# tx_board.net
KiCad netlist of a schematic drawn in Altium Designer
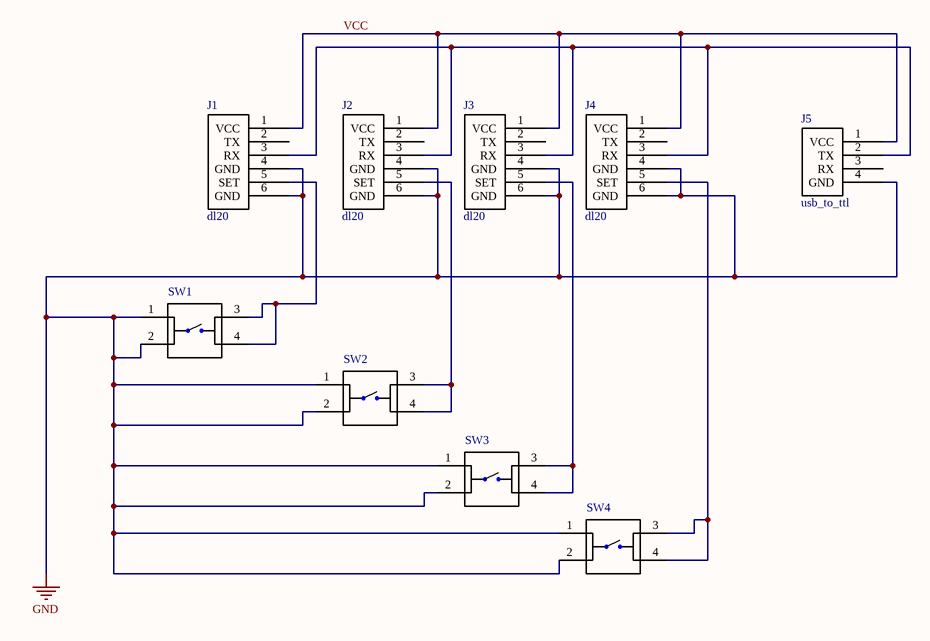
[diagram p0: tx_board.SchDoc]

(export (version "E")
  (design (tool "Eeschema 10.0.6"))
  (components
    (comp (ref "J1") (value "dl20") (footprint "DL20") (libsource (lib "Schlib2") (part "dl20")))
    (comp (ref "J2") (value "dl20") (footprint "DL20") (libsource (lib "Schlib2") (part "dl20")))
    (comp (ref "J3") (value "dl20") (footprint "DL20") (libsource (lib "Schlib2") (part "dl20")))
    (comp (ref "J4") (value "dl20") (footprint "DL20") (libsource (lib "Schlib2") (part "dl20")))
    (comp (ref "J5")
      (value "usb_to_ttl")
      (footprint "USB_TO_TTL")
      (libsource (lib "Schlib2") (part "usb_to_ttl"))
    )
    (comp (ref "SW1")
      (value "1825910-6")
      (footprint "*SW_1825910-6-4")
      (description "FSM4JH=6MM TACT SWITCH, HIGH TEMP")
      (fields (field (name "DIGI-KEY_PART_NUMBER") "450-1650-ND") (field (name "MF") "TE Connectivity"))
      (libsource (lib "1825910-6") (part "1825910-6"))
    )
    (comp (ref "SW2")
      (value "1825910-6")
      (footprint "*SW_1825910-6-4")
      (description "FSM4JH=6MM TACT SWITCH, HIGH TEMP")
      (fields (field (name "DIGI-KEY_PART_NUMBER") "450-1650-ND") (field (name "MF") "TE Connectivity"))
      (libsource (lib "1825910-6") (part "1825910-6"))
    )
    (comp (ref "SW3")
      (value "1825910-6")
      (footprint "*SW_1825910-6-4")
      (description "FSM4JH=6MM TACT SWITCH, HIGH TEMP")
      (fields (field (name "DIGI-KEY_PART_NUMBER") "450-1650-ND") (field (name "MF") "TE Connectivity"))
      (libsource (lib "1825910-6") (part "1825910-6"))
    )
    (comp (ref "SW4")
      (value "1825910-6")
      (footprint "*SW_1825910-6-4")
      (description "FSM4JH=6MM TACT SWITCH, HIGH TEMP")
      (fields (field (name "DIGI-KEY_PART_NUMBER") "450-1650-ND") (field (name "MF") "TE Connectivity"))
      (libsource (lib "1825910-6") (part "1825910-6"))
    )
  )
  (nets
    (net (code "1") (name "/VCC") (class "Default")
      (node (ref "J1") (pin "1") (pinfunction "VCC_1") (pintype "power_in"))
      (node (ref "J2") (pin "1") (pinfunction "VCC_1") (pintype "power_in"))
      (node (ref "J3") (pin "1") (pinfunction "VCC_1") (pintype "power_in"))
      (node (ref "J4") (pin "1") (pinfunction "VCC_1") (pintype "power_in"))
      (node (ref "J5") (pin "1") (pinfunction "VCC_1") (pintype "passive"))
    )
    (net (code "2") (name "GND") (class "Default")
      (node (ref "J1") (pin "4") (pinfunction "GND_4") (pintype "power_in"))
      (node (ref "J1") (pin "6") (pinfunction "GND_6") (pintype "power_in"))
      (node (ref "J2") (pin "4") (pinfunction "GND_4") (pintype "power_in"))
      (node (ref "J2") (pin "6") (pinfunction "GND_6") (pintype "power_in"))
      (node (ref "J3") (pin "4") (pinfunction "GND_4") (pintype "power_in"))
      (node (ref "J3") (pin "6") (pinfunction "GND_6") (pintype "power_in"))
      (node (ref "J4") (pin "4") (pinfunction "GND_4") (pintype "power_in"))
      (node (ref "J4") (pin "6") (pinfunction "GND_6") (pintype "power_in"))
      (node (ref "J5") (pin "4") (pinfunction "GND_4") (pintype "passive"))
      (node (ref "SW1") (pin "1") (pinfunction "1_1") (pintype "passive"))
      (node (ref "SW1") (pin "2") (pinfunction "2_2") (pintype "passive"))
      (node (ref "SW2") (pin "1") (pinfunction "1_1") (pintype "passive"))
      (node (ref "SW2") (pin "2") (pinfunction "2_2") (pintype "passive"))
      (node (ref "SW3") (pin "1") (pinfunction "1_1") (pintype "passive"))
      (node (ref "SW3") (pin "2") (pinfunction "2_2") (pintype "passive"))
      (node (ref "SW4") (pin "1") (pinfunction "1_1") (pintype "passive"))
      (node (ref "SW4") (pin "2") (pinfunction "2_2") (pintype "passive"))
    )
    (net (code "3") (name "Net-(J1-RX)") (class "Default")
      (node (ref "J1") (pin "3") (pinfunction "RX_3") (pintype "passive"))
      (node (ref "J2") (pin "3") (pinfunction "RX_3") (pintype "passive"))
      (node (ref "J3") (pin "3") (pinfunction "RX_3") (pintype "passive"))
      (node (ref "J4") (pin "3") (pinfunction "RX_3") (pintype "passive"))
      (node (ref "J5") (pin "2") (pinfunction "TX_2") (pintype "passive"))
    )
    (net (code "4") (name "Net-(J1-SET)") (class "Default")
      (node (ref "J1") (pin "5") (pinfunction "SET_5") (pintype "passive"))
      (node (ref "SW1") (pin "3") (pinfunction "3_3") (pintype "passive"))
      (node (ref "SW1") (pin "4") (pinfunction "4_4") (pintype "passive"))
    )
    (net (code "5") (name "Net-(J2-SET)") (class "Default")
      (node (ref "J2") (pin "5") (pinfunction "SET_5") (pintype "passive"))
      (node (ref "SW2") (pin "3") (pinfunction "3_3") (pintype "passive"))
      (node (ref "SW2") (pin "4") (pinfunction "4_4") (pintype "passive"))
    )
    (net (code "6") (name "Net-(J3-SET)") (class "Default")
      (node (ref "J3") (pin "5") (pinfunction "SET_5") (pintype "passive"))
      (node (ref "SW3") (pin "3") (pinfunction "3_3") (pintype "passive"))
      (node (ref "SW3") (pin "4") (pinfunction "4_4") (pintype "passive"))
    )
    (net (code "7") (name "Net-(J4-SET)") (class "Default")
      (node (ref "J4") (pin "5") (pinfunction "SET_5") (pintype "passive"))
      (node (ref "SW4") (pin "3") (pinfunction "3_3") (pintype "passive"))
      (node (ref "SW4") (pin "4") (pinfunction "4_4") (pintype "passive"))
    )
    (net (code "8") (name "unconnected-(J1-TX-Pad2)") (class "Default")
      (node (ref "J1") (pin "2") (pinfunction "TX_2") (pintype "passive"))
    )
    (net (code "9") (name "unconnected-(J2-TX-Pad2)") (class "Default")
      (node (ref "J2") (pin "2") (pinfunction "TX_2") (pintype "passive"))
    )
    (net (code "10") (name "unconnected-(J3-TX-Pad2)") (class "Default")
      (node (ref "J3") (pin "2") (pinfunction "TX_2") (pintype "passive"))
    )
    (net (code "11") (name "unconnected-(J4-TX-Pad2)") (class "Default")
      (node (ref "J4") (pin "2") (pinfunction "TX_2") (pintype "passive"))
    )
    (net (code "12") (name "unconnected-(J5-RX-Pad3)") (class "Default")
      (node (ref "J5") (pin "3") (pinfunction "RX_3") (pintype "passive"))
    )
  )
)
